# CR.net
KiCad netlist of a schematic drawn in Altium Designer
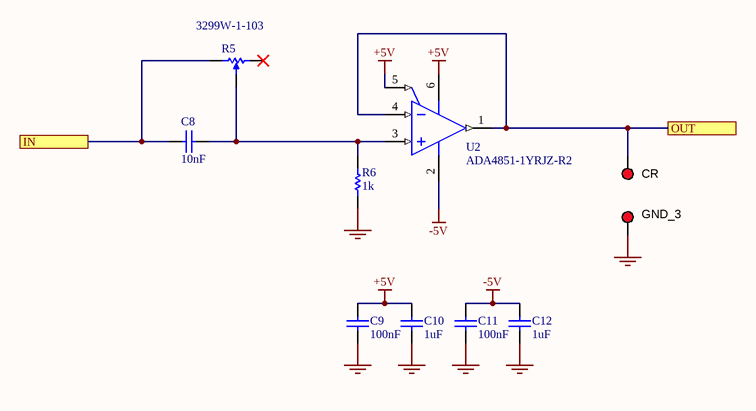
[diagram p0: CR.SchDoc]

(export (version "E")
  (design (tool "Eeschema 10.0.6"))
  (components
    (comp (ref "C8")
      (value "10nF")
      (footprint "CAPC0603(1608)100_N")
      (description "10nF Film")
      (fields (field (name "TOLERANCE") "Â±20%"))
      (libsource (lib "Altium Content Vault") (part "CAP"))
    )
    (comp (ref "C9")
      (value "100nF")
      (footprint "CAPC0603(1608)100_N")
      (description "CAP 100nF 25V ±20% 0603 (1608 Metric) Thickness 1mm SMD")
      (fields (field (name "TOLERANCE") "Â±20%"))
      (libsource (lib "Altium Content Vault") (part "CAP"))
    )
    (comp (ref "C10")
      (value "1uF")
      (footprint "CAPC0603(1608)100_N")
      (description "CAP 1uF 25V ±20% 0603 (1608 Metric) Thickness 1mm SMD")
      (fields (field (name "TOLERANCE") "Â±20%"))
      (libsource (lib "Altium Content Vault") (part "CAP"))
    )
    (comp (ref "C11")
      (value "100nF")
      (footprint "CAPC0603(1608)100_N")
      (description "CAP 100nF 25V ±20% 0603 (1608 Metric) Thickness 1mm SMD")
      (fields (field (name "TOLERANCE") "Â±20%"))
      (libsource (lib "Altium Content Vault") (part "CAP"))
    )
    (comp (ref "C12")
      (value "1uF")
      (footprint "CAPC0603(1608)100_N")
      (description "CAP 1uF 25V ±20% 0603 (1608 Metric) Thickness 1mm SMD")
      (fields (field (name "TOLERANCE") "Â±20%"))
      (libsource (lib "Altium Content Vault") (part "CAP"))
    )
    (comp (ref "CR")
      (value "5010")
      (footprint "KSTN-5010_V")
      (description "Test Point, Red, Through Hole, RoHS, Bulk")
      (libsource (lib "Altium Content Vault") (part "TESTPOINT_RED"))
    )
    (comp (ref "GND_3")
      (value "5010")
      (footprint "KSTN-5010_V")
      (description "Test Point, Red, Through Hole, RoHS, Bulk")
      (libsource (lib "Altium Content Vault") (part "TESTPOINT_RED"))
    )
    (comp (ref "R5")
      (value "3299W-1-103")
      (footprint "BOUR-3299W-3_V")
      (fields (field (name "MANUFACTURER") "Bourns") (field (name "TOLERANCE") "10%"))
      (libsource (lib "Altium Content Vault") (part "RES-ADJ-3_A"))
    )
    (comp (ref "R6")
      (value "1k")
      (footprint "RESC0603(1608)_N")
      (description "1k 1% Metal film")
      (fields (field (name "TOLERANCE") "1 %") (field (name "POWER") "0.1 W"))
      (libsource (lib "Altium Content Vault") (part "RES"))
    )
    (comp (ref "U2")
      (value "ADA4851-1YRJZ-R2")
      (footprint "ADI-RJ-6_N")
      (fields (field (name "GENERIC PART NUMBER") "ADA4851-1") (field (name "MANUFACTURER") "Analog Devices"))
      (libsource (lib "Altium Content Vault") (part "ADI-ADA48X1-1-RJ-6"))
    )
  )
  (nets
    (net (code "1") (name "+5V") (class "Default")
      (node (ref "C10") (pin "2") (pinfunction "2_2") (pintype "passive"))
      (node (ref "C9") (pin "2") (pinfunction "2_2") (pintype "passive"))
      (node (ref "U2") (pin "5") (pinfunction "~{POWER_DOWN}_5") (pintype "input"))
      (node (ref "U2") (pin "6") (pinfunction "+VS_6") (pintype "power_in"))
    )
    (net (code "2") (name "-5V") (class "Default")
      (node (ref "C11") (pin "2") (pinfunction "2_2") (pintype "passive"))
      (node (ref "C12") (pin "2") (pinfunction "2_2") (pintype "passive"))
      (node (ref "U2") (pin "2") (pinfunction "-VS_2") (pintype "power_in"))
    )
    (net (code "3") (name "/IN") (class "Default")
      (node (ref "C8") (pin "2") (pinfunction "2_2") (pintype "passive"))
      (node (ref "R5") (pin "1") (pinfunction "1_1") (pintype "passive"))
    )
    (net (code "4") (name "/OUT") (class "Default")
      (node (ref "CR") (pin "1") (pinfunction "1_1") (pintype "passive"))
      (node (ref "U2") (pin "1") (pinfunction "VOUT_1") (pintype "output"))
      (node (ref "U2") (pin "4") (pinfunction "-IN_4") (pintype "input"))
    )
    (net (code "5") (name "GND") (class "Default")
      (node (ref "C10") (pin "1") (pinfunction "1_1") (pintype "passive"))
      (node (ref "C11") (pin "1") (pinfunction "1_1") (pintype "passive"))
      (node (ref "C12") (pin "1") (pinfunction "1_1") (pintype "passive"))
      (node (ref "C9") (pin "1") (pinfunction "1_1") (pintype "passive"))
      (node (ref "GND_3") (pin "1") (pinfunction "1_1") (pintype "passive"))
      (node (ref "R6") (pin "1") (pinfunction "1_1") (pintype "passive"))
    )
    (net (code "6") (name "Net-(U2-+IN)") (class "Default")
      (node (ref "C8") (pin "1") (pinfunction "1_1") (pintype "passive"))
      (node (ref "R5") (pin "2") (pinfunction "2_2") (pintype "passive"))
      (node (ref "R6") (pin "2") (pinfunction "2_2") (pintype "passive"))
      (node (ref "U2") (pin "3") (pinfunction "+IN_3") (pintype "input"))
    )
    (net (code "7") (name "unconnected-(R5-Pad3)") (class "Default")
      (node (ref "R5") (pin "3") (pinfunction "3_3") (pintype "passive+no_connect"))
    )
  )
)
